# TailDisk.net
KiCad netlist of a schematic drawn in EAGLE
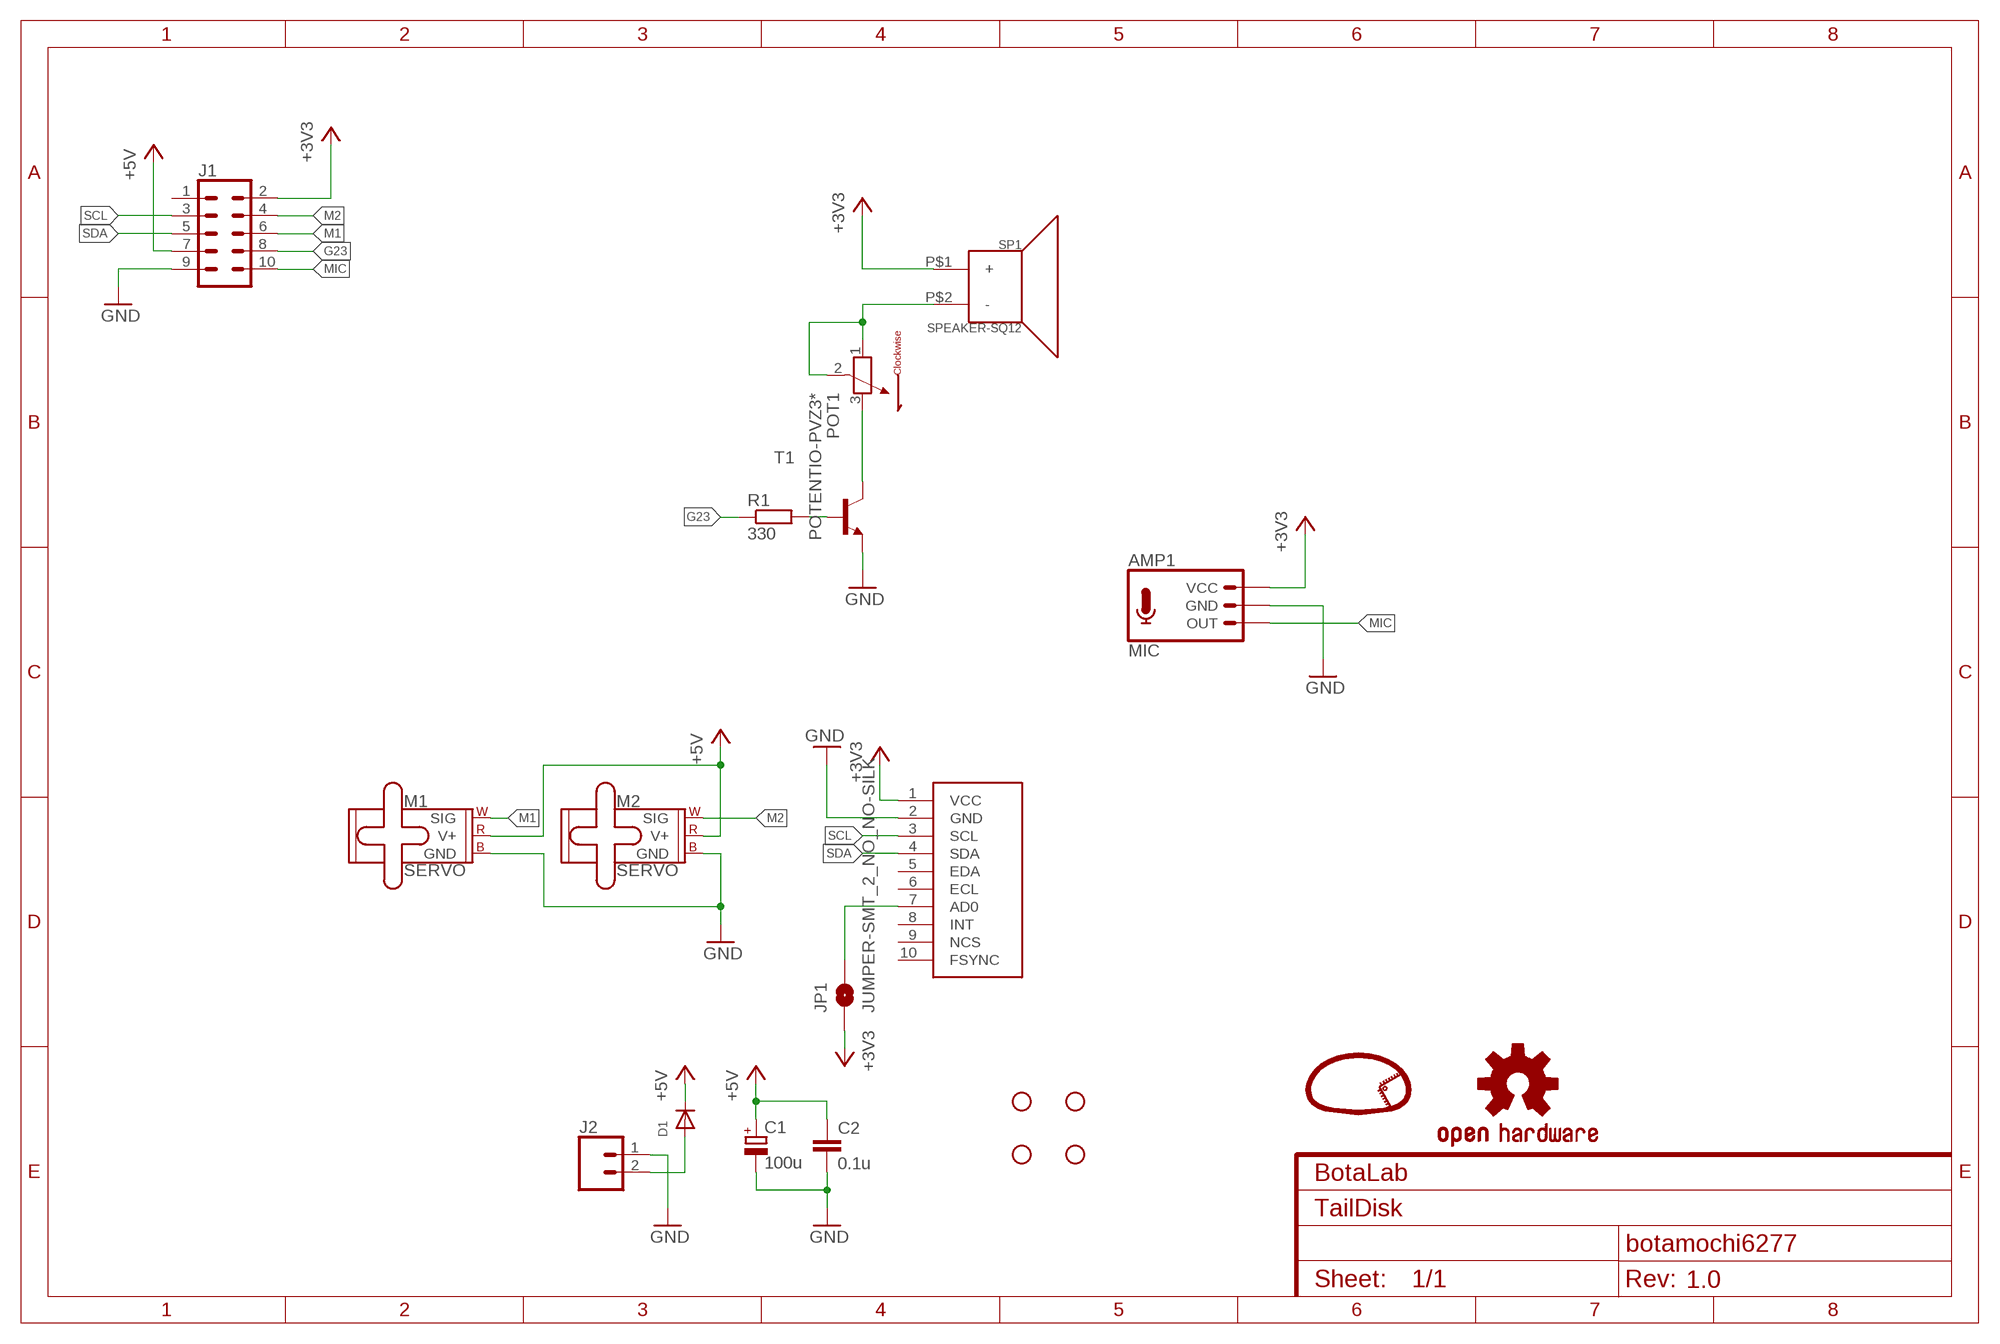
[diagram p0: schematic, sheet 1]

(export (version "E")
  (design (tool "Eeschema 10.0.6"))
  (components
    (comp (ref "AMP1")
      (value "MIC")
      (footprint "eagle-import:ADAFRUIT-1063")
      (libsource (lib "eagle-import") (part "MIC"))
    )
    (comp (ref "C1")
      (value "100u")
      (footprint "eagle-import:153CLV-0605")
      (libsource (lib "eagle-import") (part "CPOL-EU153CLV-0605"))
    )
    (comp (ref "C2")
      (value "0.1u")
      (footprint "eagle-import:C1608")
      (libsource (lib "eagle-import") (part "C-EUC1608"))
    )
    (comp (ref "D1")
      (value "DIODE_SOD-123FL")
      (footprint "eagle-import:SOD-123FL")
      (libsource (lib "eagle-import") (part "DIODE_SOD-123FL"))
    )
    (comp (ref "H1")
      (value "STAND-OFF3.3")
      (footprint "eagle-import:STAND-OFF-3.3")
      (libsource (lib "eagle-import") (part "STAND-OFF3.3"))
    )
    (comp (ref "H2")
      (value "STAND-OFF3.3")
      (footprint "eagle-import:STAND-OFF-3.3")
      (libsource (lib "eagle-import") (part "STAND-OFF3.3"))
    )
    (comp (ref "H3")
      (value "STAND-OFF3.3")
      (footprint "eagle-import:STAND-OFF-3.3")
      (libsource (lib "eagle-import") (part "STAND-OFF3.3"))
    )
    (comp (ref "H4")
      (value "STAND-OFF3.3")
      (footprint "eagle-import:STAND-OFF-3.3")
      (libsource (lib "eagle-import") (part "STAND-OFF3.3"))
    )
    (comp (ref "IC1")
      (value "IMU-MODULE")
      (footprint "eagle-import:IMU-MODULE")
      (libsource (lib "eagle-import") (part "IMU-MODULE"))
    )
    (comp (ref "J1")
      (value "CONN_05X2RA")
      (footprint "eagle-import:2X5-RA")
      (libsource (lib "eagle-import") (part "CONN_05X2RA"))
    )
    (comp (ref "J2")
      (value "CONN_02-JST-2MM-SMT")
      (footprint "eagle-import:JST-2-SMD")
      (libsource (lib "eagle-import") (part "CONN_02-JST-2MM-SMT"))
    )
    (comp (ref "JP1")
      (value "JUMPER-SMT_2_NO_NO-SILK")
      (footprint "eagle-import:SMT-JUMPER_2_NO_NO-SILK")
      (libsource (lib "eagle-import") (part "JUMPER-SMT_2_NO_NO-SILK"))
    )
    (comp (ref "LOGO1")
      (value "LOGO")
      (footprint "eagle-import:LOGO")
      (libsource (lib "eagle-import") (part "LOGO"))
    )
    (comp (ref "LOGO2")
      (value "OSHW-LOGOS")
      (footprint "eagle-import:OSHW-LOGO-S")
      (libsource (lib "eagle-import") (part "OSHW-LOGOS"))
    )
    (comp (ref "M1")
      (value "SERVO")
      (footprint "eagle-import:1X03")
      (libsource (lib "eagle-import") (part "SERVO"))
    )
    (comp (ref "M2")
      (value "SERVO")
      (footprint "eagle-import:1X03")
      (libsource (lib "eagle-import") (part "SERVO"))
    )
    (comp (ref "POT1")
      (value "POTENTIO-PVZ3*")
      (footprint "eagle-import:PVZ3_")
      (libsource (lib "eagle-import") (part "POTENTIO-PVZ3"))
    )
    (comp (ref "R1")
      (value "330")
      (footprint "eagle-import:R0603")
      (libsource (lib "eagle-import") (part "R-EU_R0603"))
    )
    (comp (ref "SP1")
      (value "SPEAKER-SQ12")
      (footprint "eagle-import:PKLCS1212E")
      (libsource (lib "eagle-import") (part "SPEAKER-SQ12"))
    )
    (comp (ref "T1")
      (value "MMUN2211LT1-NPN-SC59-BEC")
      (footprint "eagle-import:SC59-BEC")
      (libsource (lib "eagle-import") (part "-NPN-SC59-BECMMUN2211LT1"))
    )
  )
  (nets
    (net (code "1") (name "+3V3") (class "Default")
      (node (ref "AMP1") (pin "P$3") (pinfunction "VCC_P$3") (pintype "power_in"))
      (node (ref "IC1") (pin "1") (pinfunction "VCC_1") (pintype "power_in"))
      (node (ref "J1") (pin "2") (pinfunction "2_2") (pintype "passive"))
      (node (ref "JP1") (pin "1") (pinfunction "1_1") (pintype "passive"))
      (node (ref "SP1") (pin "P$1") (pinfunction "+_P$1") (pintype "bidirectional"))
    )
    (net (code "2") (name "+5V") (class "Default")
      (node (ref "C1") (pin "+") (pinfunction "+_+") (pintype "passive"))
      (node (ref "C2") (pin "1") (pinfunction "1_1") (pintype "passive"))
      (node (ref "D1") (pin "C") (pinfunction "C_C") (pintype "passive"))
      (node (ref "J1") (pin "7") (pinfunction "7_7") (pintype "passive"))
      (node (ref "M1") (pin "2") (pinfunction "V+_2") (pintype "bidirectional"))
      (node (ref "M2") (pin "2") (pinfunction "V+_2") (pintype "bidirectional"))
    )
    (net (code "3") (name "G23") (class "Default")
      (node (ref "J1") (pin "8") (pinfunction "8_8") (pintype "passive"))
      (node (ref "R1") (pin "1") (pinfunction "1_1") (pintype "passive"))
    )
    (net (code "4") (name "GND") (class "Default")
      (node (ref "AMP1") (pin "P$2") (pinfunction "GND_P$2") (pintype "power_in"))
      (node (ref "C1") (pin "-") (pinfunction "-_-") (pintype "passive"))
      (node (ref "C2") (pin "2") (pinfunction "2_2") (pintype "passive"))
      (node (ref "IC1") (pin "2") (pinfunction "GND_2") (pintype "power_in"))
      (node (ref "J1") (pin "9") (pinfunction "9_9") (pintype "passive"))
      (node (ref "J2") (pin "1") (pinfunction "2_1") (pintype "passive"))
      (node (ref "M1") (pin "3") (pinfunction "GND_3") (pintype "bidirectional"))
      (node (ref "M2") (pin "3") (pinfunction "GND_3") (pintype "bidirectional"))
      (node (ref "T1") (pin "E") (pinfunction "E_E") (pintype "passive"))
    )
    (net (code "5") (name "M1") (class "Default")
      (node (ref "J1") (pin "6") (pinfunction "6_6") (pintype "passive"))
      (node (ref "M1") (pin "1") (pinfunction "SIG_1") (pintype "bidirectional"))
    )
    (net (code "6") (name "M2") (class "Default")
      (node (ref "J1") (pin "4") (pinfunction "4_4") (pintype "passive"))
      (node (ref "M2") (pin "1") (pinfunction "SIG_1") (pintype "bidirectional"))
    )
    (net (code "7") (name "MIC") (class "Default")
      (node (ref "AMP1") (pin "P$1") (pinfunction "OUT_P$1") (pintype "output"))
      (node (ref "J1") (pin "10") (pinfunction "10_10") (pintype "passive"))
    )
    (net (code "8") (name "Net-(IC1-AD0)") (class "Default")
      (node (ref "IC1") (pin "7") (pinfunction "AD0_7") (pintype "bidirectional"))
      (node (ref "JP1") (pin "2") (pinfunction "2_2") (pintype "passive"))
    )
    (net (code "9") (name "Net-(J2-1)") (class "Default")
      (node (ref "D1") (pin "A") (pinfunction "A_A") (pintype "passive"))
      (node (ref "J2") (pin "2") (pinfunction "1_2") (pintype "passive"))
    )
    (net (code "10") (name "Net-(POT1-Pad3)") (class "Default")
      (node (ref "POT1") (pin "3") (pinfunction "3_3") (pintype "passive"))
      (node (ref "T1") (pin "C") (pinfunction "C_C") (pintype "passive"))
    )
    (net (code "11") (name "Net-(R1-Pad2)") (class "Default")
      (node (ref "R1") (pin "2") (pinfunction "2_2") (pintype "passive"))
      (node (ref "T1") (pin "B") (pinfunction "B_B") (pintype "passive"))
    )
    (net (code "12") (name "Net-(SP1--)") (class "Default")
      (node (ref "POT1") (pin "1") (pinfunction "1_1") (pintype "passive"))
      (node (ref "POT1") (pin "2") (pinfunction "2_2") (pintype "passive"))
      (node (ref "SP1") (pin "P$2") (pinfunction "-_P$2") (pintype "bidirectional"))
    )
    (net (code "13") (name "SCL") (class "Default")
      (node (ref "IC1") (pin "3") (pinfunction "SCL_3") (pintype "bidirectional"))
      (node (ref "J1") (pin "3") (pinfunction "3_3") (pintype "passive"))
    )
    (net (code "14") (name "SDA") (class "Default")
      (node (ref "IC1") (pin "4") (pinfunction "SDA_4") (pintype "bidirectional"))
      (node (ref "J1") (pin "5") (pinfunction "5_5") (pintype "passive"))
    )
    (net (code "15") (name "unconnected-(IC1-ECL-Pad6)") (class "Default")
      (node (ref "IC1") (pin "6") (pinfunction "ECL_6") (pintype "bidirectional"))
    )
    (net (code "16") (name "unconnected-(IC1-EDA-Pad5)") (class "Default")
      (node (ref "IC1") (pin "5") (pinfunction "EDA_5") (pintype "bidirectional"))
    )
    (net (code "17") (name "unconnected-(IC1-FSYNC-Pad10)") (class "Default")
      (node (ref "IC1") (pin "10") (pinfunction "FSYNC_10") (pintype "bidirectional"))
    )
    (net (code "18") (name "unconnected-(IC1-INT-Pad8)") (class "Default")
      (node (ref "IC1") (pin "8") (pinfunction "INT_8") (pintype "bidirectional"))
    )
    (net (code "19") (name "unconnected-(IC1-NCS-Pad9)") (class "Default")
      (node (ref "IC1") (pin "9") (pinfunction "NCS_9") (pintype "bidirectional"))
    )
    (net (code "20") (name "unconnected-(J1-Pad1)") (class "Default")
      (node (ref "J1") (pin "1") (pinfunction "1_1") (pintype "passive"))
    )
  )
)
